# N25Q128A13ESE40.net
KiCad netlist of a schematic drawn in Altium Designer
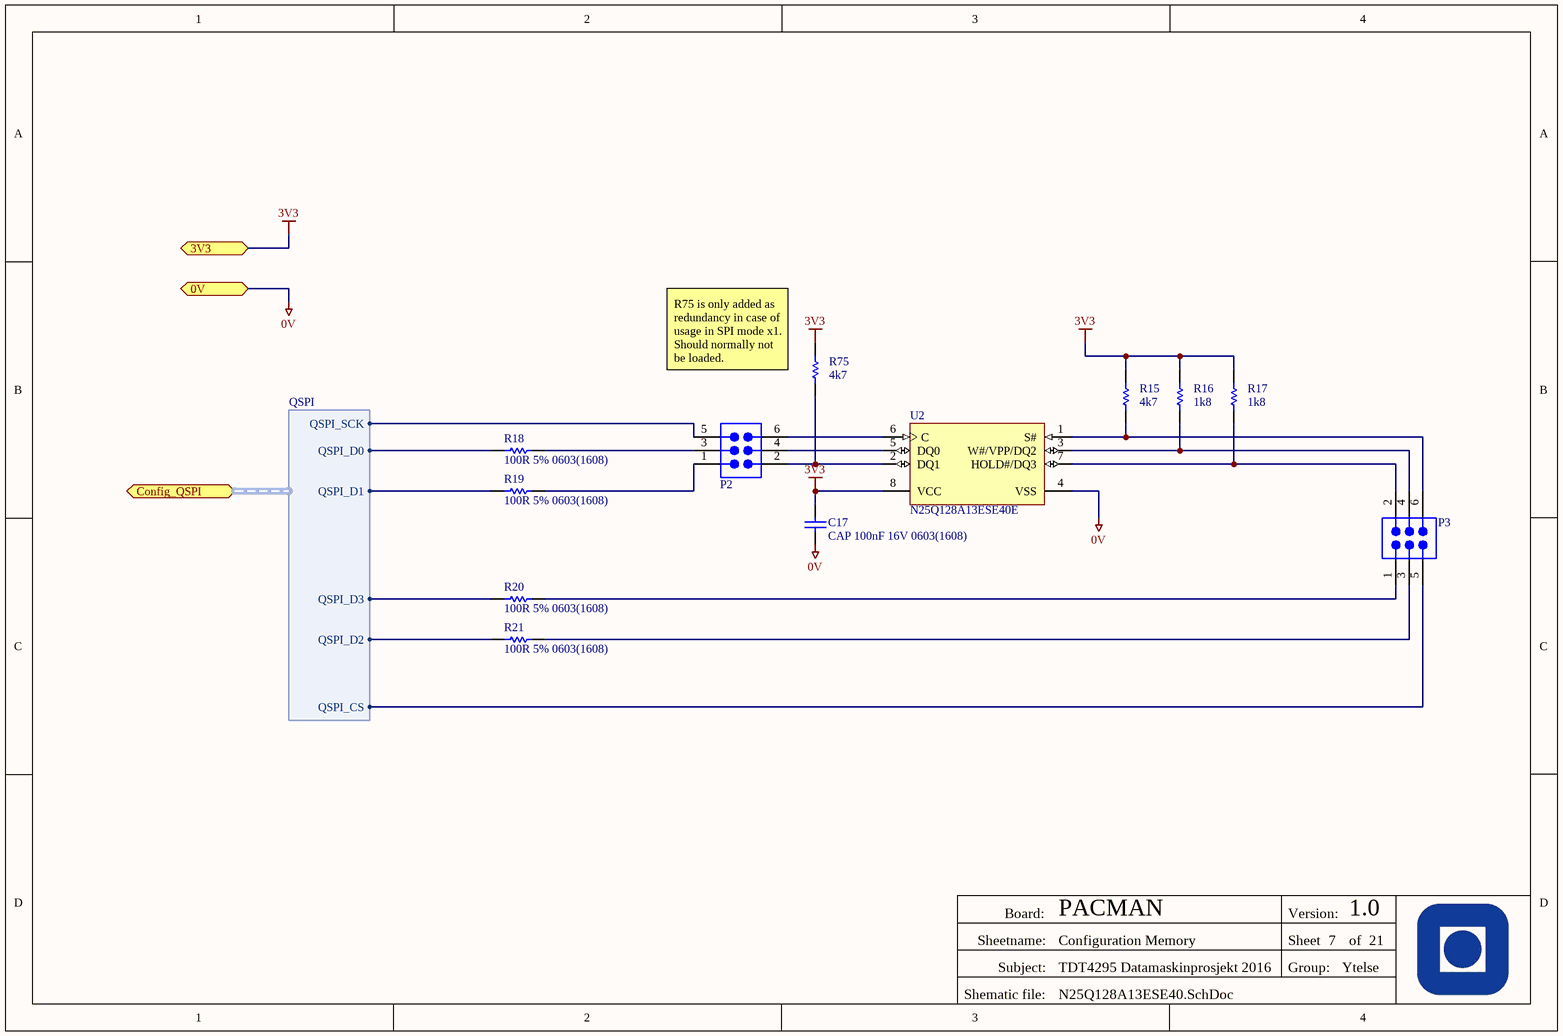
[diagram p0: N25Q128A13ESE40.SchDoc]

(export (version "E")
  (design (tool "Eeschema 10.0.6"))
  (components
    (comp (ref "C17")
      (value "CAP 100nF 16V 0603(1608)")
      (footprint "CAPC0603(1608)100_M")
      (description "CAP 100nF 16V ±5% 0603 (1608 Metric) Thickness 1mm SMD")
      (fields (field (name "TOLERANCE") "Â±5%"))
      (libsource (lib "Altium Content Vault") (part "CAP"))
    )
    (comp (ref "P2")
      (value "TSW-103-08-T-D")
      (footprint "SMTC-TSW-103-08-X-D")
      (description "0.025\" SQ Post Header, Through-hole, Vertical, -55 to 105 degC, 2.54 mm Pitch, 6-Pin, Male, RoHS")
      (fields (field (name "MANUFACTURER") "Samtec"))
      (libsource (lib "Altium Content Vault") (part "CMP-1024-00335-1"))
    )
    (comp (ref "P3")
      (value "TSW-103-08-T-D")
      (footprint "SMTC-TSW-103-08-X-D")
      (description "0.025\" SQ Post Header, Through-hole, Vertical, -55 to 105 degC, 2.54 mm Pitch, 6-Pin, Male, RoHS")
      (fields (field (name "MANUFACTURER") "Samtec"))
      (libsource (lib "Altium Content Vault") (part "CMP-1024-00335-1"))
    )
    (comp (ref "R15")
      (value "4k7")
      (footprint "RESC0603(1608)_M")
      (description "4K7 0.1W 5% 0603 (1608 Metric)  SMD")
      (fields (field (name "TOLERANCE") "5 %") (field (name "POWER") "0.1 W"))
      (libsource (lib "Altium Content Vault") (part "CMP-1012-00090-1"))
    )
    (comp (ref "R16")
      (value "1k8")
      (footprint "RESC0603(1608)_M")
      (description "1K8 0.1W 5% 0603 (1608 Metric)  SMD")
      (fields (field (name "TOLERANCE") "5 %") (field (name "POWER") "0.1 W"))
      (libsource (lib "Altium Content Vault") (part "CMP-1012-00080-1"))
    )
    (comp (ref "R17")
      (value "1k8")
      (footprint "RESC0603(1608)_M")
      (description "1K8 0.1W 5% 0603 (1608 Metric)  SMD")
      (fields (field (name "TOLERANCE") "5 %") (field (name "POWER") "0.1 W"))
      (libsource (lib "Altium Content Vault") (part "CMP-1012-00080-1"))
    )
    (comp (ref "R18")
      (value "100R 5% 0603(1608)")
      (footprint "RESC0603(1608)_M")
      (description "100R 0.1W 5% 0603 (1608 Metric)  SMD")
      (fields (field (name "TOLERANCE") "5 %") (field (name "POWER") "0.1 W"))
      (libsource (lib "Altium Content Vault") (part "CMP-1012-00050-1"))
    )
    (comp (ref "R19")
      (value "100R 5% 0603(1608)")
      (footprint "RESC0603(1608)_M")
      (description "100R 0.1W 5% 0603 (1608 Metric)  SMD")
      (fields (field (name "TOLERANCE") "5 %") (field (name "POWER") "0.1 W"))
      (libsource (lib "Altium Content Vault") (part "CMP-1012-00050-1"))
    )
    (comp (ref "R20")
      (value "100R 5% 0603(1608)")
      (footprint "RESC0603(1608)_M")
      (description "100R 0.1W 5% 0603 (1608 Metric)  SMD")
      (fields (field (name "TOLERANCE") "5 %") (field (name "POWER") "0.1 W"))
      (libsource (lib "Altium Content Vault") (part "CMP-1012-00050-1"))
    )
    (comp (ref "R21")
      (value "100R 5% 0603(1608)")
      (footprint "RESC0603(1608)_M")
      (description "100R 0.1W 5% 0603 (1608 Metric)  SMD")
      (fields (field (name "TOLERANCE") "5 %") (field (name "POWER") "0.1 W"))
      (libsource (lib "Altium Content Vault") (part "CMP-1012-00050-1"))
    )
    (comp (ref "R75")
      (value "4k7")
      (footprint "RESC0603(1608)_M")
      (description "4K7 0.1W 5% 0603 (1608 Metric)  SMD")
      (fields (field (name "TOLERANCE") "5 %") (field (name "POWER") "0.1 W"))
      (libsource (lib "Altium Content Vault") (part "CMP-1012-00090-1"))
    )
    (comp (ref "U2")
      (value "N25Q128A13ESE40E")
      (footprint "MICT-SE-8_N")
      (fields (field (name "VOLTAGE") "2.7V-3.6VÂ ") (field (name "MANUFACTURER") "Micron"))
      (libsource (lib "Altium Content Vault") (part "MICT-N25Q128SE-8"))
    )
  )
  (nets
    (net (code "2") (name "/QSPI_CS") (class "Default")
      (node (ref "P3") (pin "5") (pinfunction "5_5") (pintype "passive"))
    )
    (net (code "3") (name "/QSPI_D0") (class "Default")
      (node (ref "R18") (pin "2") (pinfunction "2_2") (pintype "passive"))
    )
    (net (code "4") (name "/QSPI_D1") (class "Default")
      (node (ref "R19") (pin "2") (pinfunction "2_2") (pintype "passive"))
    )
    (net (code "5") (name "/QSPI_D2") (class "Default")
      (node (ref "R21") (pin "2") (pinfunction "2_2") (pintype "passive"))
    )
    (net (code "6") (name "/QSPI_D3") (class "Default")
      (node (ref "R20") (pin "2") (pinfunction "2_2") (pintype "passive"))
    )
    (net (code "7") (name "/QSPI_SCK") (class "Default")
      (node (ref "P2") (pin "5") (pinfunction "5_5") (pintype "passive"))
    )
    (net (code "9") (name "0V") (class "Default")
      (node (ref "C17") (pin "1") (pinfunction "1_1") (pintype "passive"))
      (node (ref "U2") (pin "4") (pinfunction "VSS_4") (pintype "power_in"))
    )
    (net (code "10") (name "3V3") (class "Default")
      (node (ref "C17") (pin "2") (pinfunction "2_2") (pintype "passive"))
      (node (ref "R15") (pin "2") (pinfunction "2_2") (pintype "passive"))
      (node (ref "R16") (pin "2") (pinfunction "2_2") (pintype "passive"))
      (node (ref "R17") (pin "2") (pinfunction "2_2") (pintype "passive"))
      (node (ref "R75") (pin "2") (pinfunction "2_2") (pintype "passive"))
      (node (ref "U2") (pin "8") (pinfunction "VCC_8") (pintype "power_in"))
    )
    (net (code "11") (name "Net-(P2-Pad1)") (class "Default")
      (node (ref "P2") (pin "1") (pinfunction "1_1") (pintype "passive"))
      (node (ref "R19") (pin "1") (pinfunction "1_1") (pintype "passive"))
    )
    (net (code "12") (name "Net-(P2-Pad3)") (class "Default")
      (node (ref "P2") (pin "3") (pinfunction "3_3") (pintype "passive"))
      (node (ref "R18") (pin "1") (pinfunction "1_1") (pintype "passive"))
    )
    (net (code "13") (name "Net-(P3-Pad1)") (class "Default")
      (node (ref "P3") (pin "1") (pinfunction "1_1") (pintype "passive"))
      (node (ref "R20") (pin "1") (pinfunction "1_1") (pintype "passive"))
    )
    (net (code "14") (name "Net-(P3-Pad3)") (class "Default")
      (node (ref "P3") (pin "3") (pinfunction "3_3") (pintype "passive"))
      (node (ref "R21") (pin "1") (pinfunction "1_1") (pintype "passive"))
    )
    (net (code "15") (name "Net-(U2-C)") (class "Default")
      (node (ref "P2") (pin "6") (pinfunction "6_6") (pintype "passive"))
      (node (ref "U2") (pin "6") (pinfunction "C_6") (pintype "input"))
    )
    (net (code "16") (name "Net-(U2-DQ0)") (class "Default")
      (node (ref "P2") (pin "4") (pinfunction "4_4") (pintype "passive"))
      (node (ref "U2") (pin "5") (pinfunction "DQ0_5") (pintype "bidirectional"))
    )
    (net (code "17") (name "Net-(U2-DQ1)") (class "Default")
      (node (ref "P2") (pin "2") (pinfunction "2_2") (pintype "passive"))
      (node (ref "R75") (pin "1") (pinfunction "1_1") (pintype "passive"))
      (node (ref "U2") (pin "2") (pinfunction "DQ1_2") (pintype "bidirectional"))
    )
    (net (code "18") (name "Net-(U2-HOLD#{slash}DQ3)") (class "Default")
      (node (ref "P3") (pin "2") (pinfunction "2_2") (pintype "passive"))
      (node (ref "R17") (pin "1") (pinfunction "1_1") (pintype "passive"))
      (node (ref "U2") (pin "7") (pinfunction "HOLD#/DQ3_7") (pintype "bidirectional"))
    )
    (net (code "19") (name "Net-(U2-S#)") (class "Default")
      (node (ref "P3") (pin "6") (pinfunction "6_6") (pintype "passive"))
      (node (ref "R15") (pin "1") (pinfunction "1_1") (pintype "passive"))
      (node (ref "U2") (pin "1") (pinfunction "S#_1") (pintype "input"))
    )
    (net (code "20") (name "Net-(U2-W#{slash}VPP{slash}DQ2)") (class "Default")
      (node (ref "P3") (pin "4") (pinfunction "4_4") (pintype "passive"))
      (node (ref "R16") (pin "1") (pinfunction "1_1") (pintype "passive"))
      (node (ref "U2") (pin "3") (pinfunction "W#/VPP/DQ2_3") (pintype "bidirectional"))
    )
  )
)
